# 4_36.net
KiCad netlist of a schematic drawn in EasyEDA
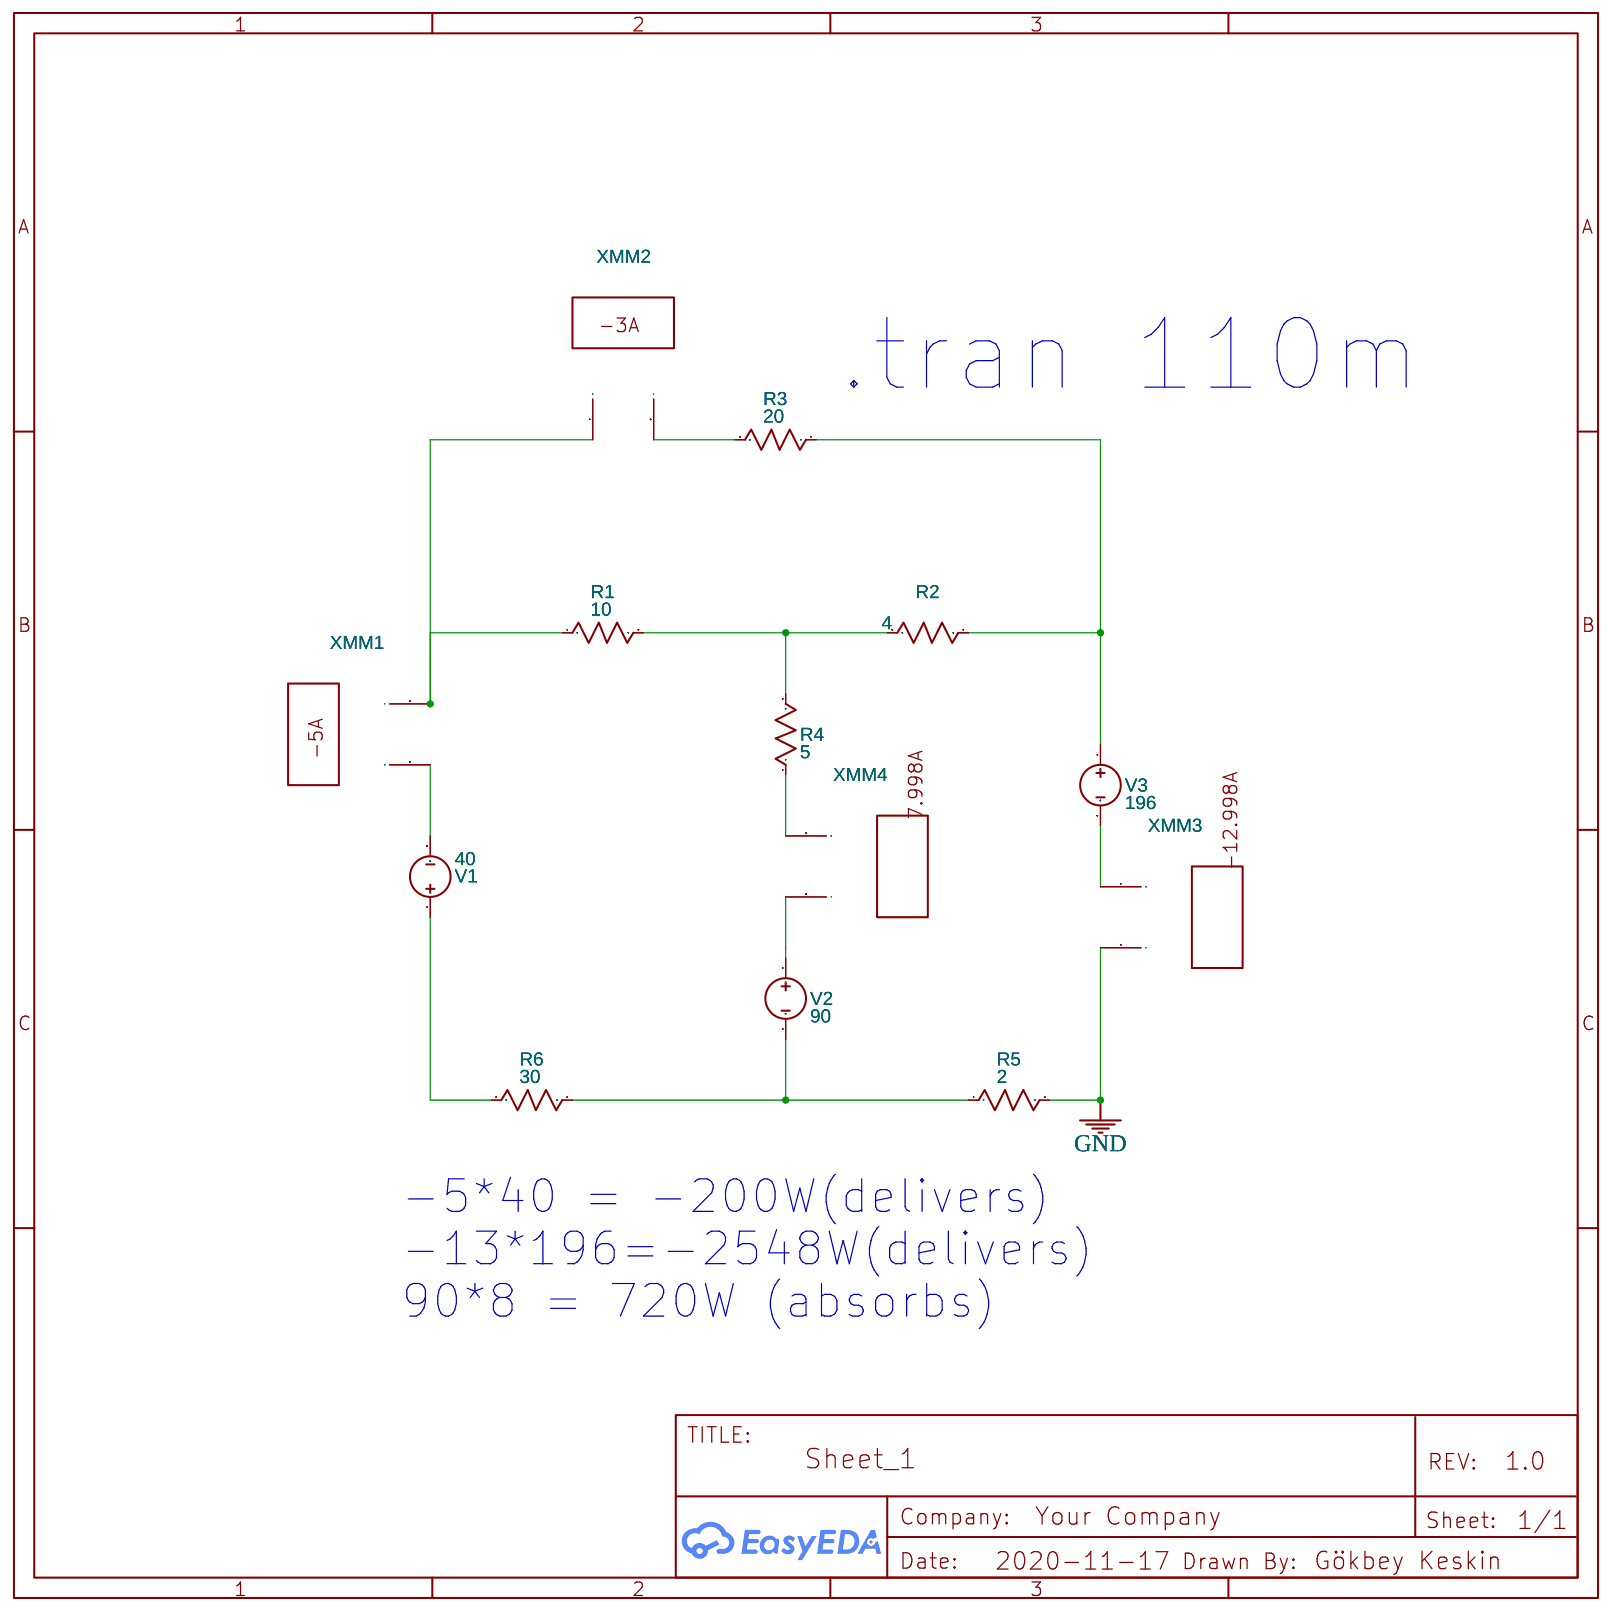
[diagram p0: schematic sheet]

(export (version "E")
  (design (tool "Eeschema 10.0.6"))
  (components
    (comp (ref "R1") (value "10") (libsource (lib "") (part "Resistor_US_1")))
    (comp (ref "R2") (value "4") (libsource (lib "") (part "Resistor_US_1")))
    (comp (ref "R3") (value "20") (libsource (lib "") (part "Resistor_US")))
    (comp (ref "R4") (value "5") (libsource (lib "") (part "Resistor_US_2")))
    (comp (ref "R5") (value "2") (libsource (lib "") (part "Resistor_US_1")))
    (comp (ref "R6") (value "30") (libsource (lib "") (part "Resistor_US_1")))
    (comp (ref "V1") (value "40") (libsource (lib "") (part "VDC_1")))
    (comp (ref "V2") (value "90") (libsource (lib "") (part "VDC")))
    (comp (ref "V3") (value "196") (libsource (lib "") (part "VDC")))
    (comp (ref "XMM1") (value "Multimeter") (libsource (lib "") (part "MULTIMETER_2")))
    (comp (ref "XMM2") (value "Multimeter") (libsource (lib "") (part "MULTIMETER_3")))
    (comp (ref "XMM3") (value "Multimeter") (libsource (lib "") (part "MULTIMETER")))
    (comp (ref "XMM4") (value "Multimeter") (libsource (lib "") (part "MULTIMETER_1")))
  )
  (nets
    (net (code "1") (name "GND") (class "Default")
      (node (ref "R5") (pin "2") (pinfunction "2_2") (pintype "unspecified"))
      (node (ref "XMM3") (pin "2") (pinfunction "I_2") (pintype "unspecified"))
    )
    (net (code "2") (name "Net-(R1-Pad2)") (class "Default")
      (node (ref "R1") (pin "2") (pinfunction "2_2") (pintype "unspecified"))
      (node (ref "R2") (pin "1") (pinfunction "1_1") (pintype "unspecified"))
      (node (ref "R4") (pin "2") (pinfunction "2_2") (pintype "unspecified"))
    )
    (net (code "3") (name "Net-(R2-Pad2)") (class "Default")
      (node (ref "R2") (pin "2") (pinfunction "2_2") (pintype "unspecified"))
      (node (ref "R3") (pin "1") (pinfunction "1_1") (pintype "unspecified"))
      (node (ref "V3") (pin "1") (pinfunction "1_1") (pintype "unspecified"))
    )
    (net (code "4") (name "Net-(R5-Pad1)") (class "Default")
      (node (ref "R5") (pin "1") (pinfunction "1_1") (pintype "unspecified"))
      (node (ref "R6") (pin "2") (pinfunction "2_2") (pintype "unspecified"))
      (node (ref "V2") (pin "2") (pinfunction "2_2") (pintype "unspecified"))
    )
    (net (code "5") (name "Net-(R6-Pad1)") (class "Default")
      (node (ref "R6") (pin "1") (pinfunction "1_1") (pintype "unspecified"))
      (node (ref "V1") (pin "1") (pinfunction "1_1") (pintype "unspecified"))
    )
    (net (code "6") (name "Net-(XMM1-+)") (class "Default")
      (node (ref "V1") (pin "2") (pinfunction "2_2") (pintype "unspecified"))
      (node (ref "XMM1") (pin "1") (pinfunction "+_1") (pintype "unspecified"))
    )
    (net (code "7") (name "Net-(XMM1-I)") (class "Default")
      (node (ref "R1") (pin "1") (pinfunction "1_1") (pintype "unspecified"))
      (node (ref "XMM1") (pin "2") (pinfunction "I_2") (pintype "unspecified"))
      (node (ref "XMM2") (pin "1") (pinfunction "+_1") (pintype "unspecified"))
    )
    (net (code "8") (name "Net-(XMM2-I)") (class "Default")
      (node (ref "R3") (pin "2") (pinfunction "2_2") (pintype "unspecified"))
      (node (ref "XMM2") (pin "2") (pinfunction "I_2") (pintype "unspecified"))
    )
    (net (code "9") (name "Net-(XMM3-+)") (class "Default")
      (node (ref "V3") (pin "2") (pinfunction "2_2") (pintype "unspecified"))
      (node (ref "XMM3") (pin "1") (pinfunction "+_1") (pintype "unspecified"))
    )
    (net (code "10") (name "Net-(XMM4-+)") (class "Default")
      (node (ref "R4") (pin "1") (pinfunction "1_1") (pintype "unspecified"))
      (node (ref "XMM4") (pin "1") (pinfunction "+_1") (pintype "unspecified"))
    )
    (net (code "11") (name "Net-(XMM4-I)") (class "Default")
      (node (ref "V2") (pin "1") (pinfunction "1_1") (pintype "unspecified"))
      (node (ref "XMM4") (pin "2") (pinfunction "I_2") (pintype "unspecified"))
    )
  )
)
